# altium.net
KiCad netlist of a schematic drawn in Altium Designer
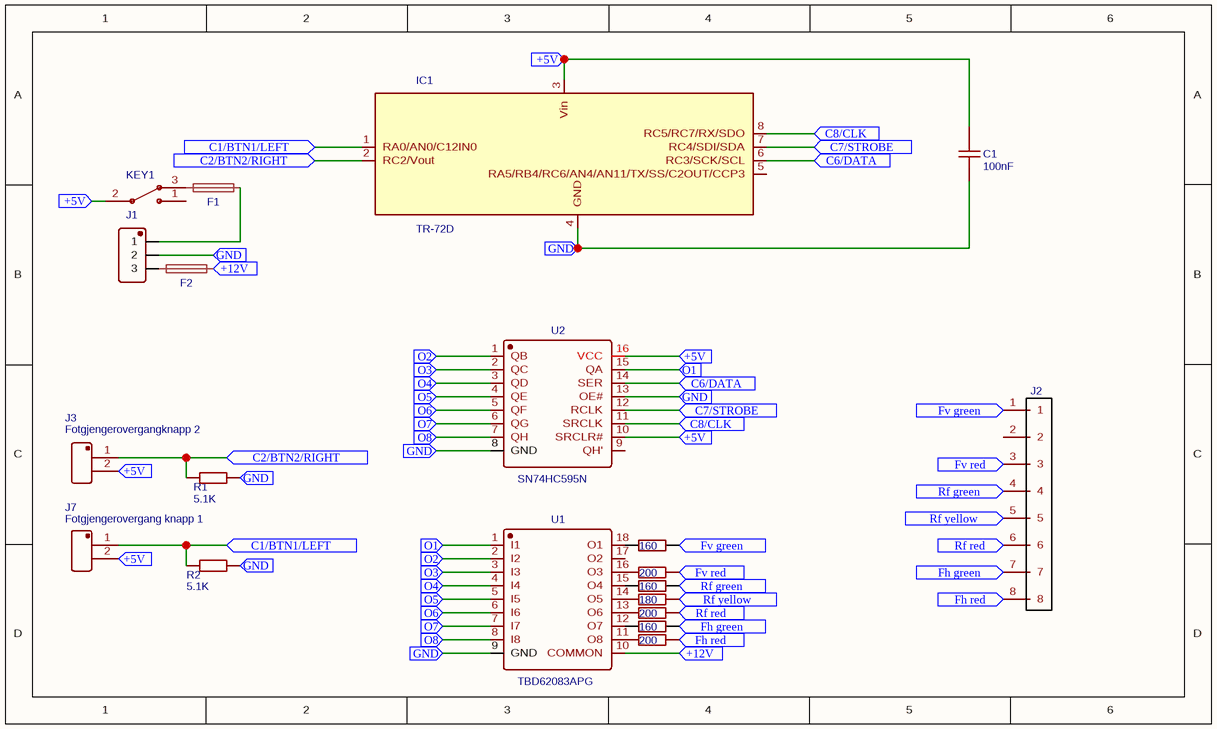
[diagram p0: altium.schdoc]

(export (version "E")
  (design (tool "Eeschema 10.0.6"))
  (components
    (comp (ref "C1")
      (value "100nF")
      (fields
        (field (name "BOM_SUPPLIER PART") "C304011")
        (field (name "BOM_MANUFACTURER PART") "1210B106K100CT")
        (field (name "CONTRIBUTOR") "LCSC")
      )
      (libsource (lib "altium-import") (part "root_3_100nF_"))
    )
    (comp (ref "F1")
      (value "NO")
      (fields
        (field (name "BOM_MANUFACTURER PART") "3403.0015.11")
        (field (name "BOM_SUPPLIER PART") "693-3403.0015.11")
        (field (name "CONTRIBUTOR") "romiksm")
      )
      (libsource (lib "altium-import") (part "root_0_NO_"))
    )
    (comp (ref "F2")
      (value "NO")
      (fields
        (field (name "BOM_MANUFACTURER PART") "3403.0015.11")
        (field (name "BOM_SUPPLIER PART") "693-3403.0015.11")
        (field (name "CONTRIBUTOR") "romiksm")
      )
      (libsource (lib "altium-import") (part "root_0_NO_"))
    )
    (comp (ref "IC1")
      (value "TR-72D")
      (fields (field (name "CONTRIBUTOR") "Simen Stensas"))
      (libsource (lib "altium-import") (part "root_0_TR-72D_"))
    )
    (comp (ref "J1")
      (value "KF127_3P_5.08")
      (fields (field (name "CONTRIBUTOR") "GrahamG"))
      (libsource (lib "altium-import") (part "root_0_KF127_3P_5.08_"))
    )
    (comp (ref "J2")
      (value "KF127-8P")
      (fields (field (name "CONTRIBUTOR") "milton.sanchez.alban"))
      (libsource (lib "altium-import") (part "root_0_KF127-8P_"))
    )
    (comp (ref "J3")
      (value "Fotgjengerovergangknapp 2")
      (fields (field (name "BOM_MANUFACTURER PART") "KF127L-5.08") (field (name "CONTRIBUTOR") "GrahamG"))
      (libsource (lib "altium-import") (part "root_0_Fotgjengerovergangknapp 2_"))
    )
    (comp (ref "J7")
      (value "Fotgjengerovergang knapp 1")
      (fields (field (name "BOM_MANUFACTURER PART") "KF127L-5.08") (field (name "CONTRIBUTOR") "GrahamG"))
      (libsource (lib "altium-import") (part "root_0_Fotgjengerovergang knapp 1_"))
    )
    (comp (ref "KEY1")
      (value "MSK-11027 Toggle Switches")
      (fields (field (name "BOM_SUPPLIER PART") "C21381"))
      (libsource (lib "altium-import") (part "root_0_MSK-11027 Toggle Switches_"))
    )
    (comp (ref "R1")
      (value "5.1K")
      (fields
        (field (name "BOM_SUPPLIER PART") "C325932")
        (field (name "BOM_MANUFACTURER PART") "RMC12065.1K1%N")
        (field (name "CONTRIBUTOR") "LCSC")
      )
      (libsource (lib "altium-import") (part "root_0_5.1K_"))
    )
    (comp (ref "R2")
      (value "5.1K")
      (fields
        (field (name "BOM_SUPPLIER PART") "C325932")
        (field (name "BOM_MANUFACTURER PART") "RMC12065.1K1%N")
        (field (name "CONTRIBUTOR") "LCSC")
      )
      (libsource (lib "altium-import") (part "root_0_5.1K_"))
    )
    (comp (ref "R8")
      (value "160")
      (fields
        (field (name "BOM_MANUFACTURER PART") "RC1206JR-07160RL")
        (field (name "BOM_SUPPLIER PART") "C137196")
      )
      (libsource (lib "altium-import") (part "root_0_160_"))
    )
    (comp (ref "R9")
      (value "160")
      (fields
        (field (name "BOM_MANUFACTURER PART") "RC1206JR-07160RL")
        (field (name "BOM_SUPPLIER PART") "C137196")
      )
      (libsource (lib "altium-import") (part "root_0_160_"))
    )
    (comp (ref "R10")
      (value "160")
      (fields
        (field (name "BOM_MANUFACTURER PART") "RC1206JR-07160RL")
        (field (name "BOM_SUPPLIER PART") "C137196")
      )
      (libsource (lib "altium-import") (part "root_0_160_"))
    )
    (comp (ref "R12")
      (value "180")
      (fields
        (field (name "BOM_SUPPLIER PART") "C204708")
        (field (name "BOM_MANUFACTURER PART") "CR1206-FX-1800ELF")
        (field (name "CONTRIBUTOR") "LCSC")
      )
      (libsource (lib "altium-import") (part "root_0_180_"))
    )
    (comp (ref "R13")
      (value "200")
      (fields
        (field (name "BOM_MANUFACTURER PART") "QR1206J200RP05")
        (field (name "BOM_SUPPLIER PART") "C149886")
        (field (name "CONTRIBUTOR") "LCSC")
      )
      (libsource (lib "altium-import") (part "root_0_200_"))
    )
    (comp (ref "R14")
      (value "200")
      (fields
        (field (name "BOM_MANUFACTURER PART") "QR1206J200RP05")
        (field (name "BOM_SUPPLIER PART") "C149886")
        (field (name "CONTRIBUTOR") "LCSC")
      )
      (libsource (lib "altium-import") (part "root_0_200_"))
    )
    (comp (ref "R15")
      (value "200")
      (fields
        (field (name "BOM_MANUFACTURER PART") "QR1206J200RP05")
        (field (name "BOM_SUPPLIER PART") "C149886")
        (field (name "CONTRIBUTOR") "LCSC")
      )
      (libsource (lib "altium-import") (part "root_0_200_"))
    )
    (comp (ref "U1")
      (value "TBD62083APG")
      (fields (field (name "BOM_SUPPLIER PART") "C114143") (field (name "CONTRIBUTOR") "LCSC"))
      (libsource (lib "altium-import") (part "root_0_TBD62083APG_"))
    )
    (comp (ref "U2")
      (value "SN74HC595N")
      (fields (field (name "BOM_SUPPLIER PART") "C78711"))
      (libsource (lib "altium-import") (part "root_0_SN74HC595N_"))
    )
  )
  (nets
    (net (code "1") (name "/+5V") (class "Default")
      (node (ref "C1") (pin "2") (pinfunction "2_2") (pintype "passive"))
      (node (ref "IC1") (pin "3") (pinfunction "Vin_3") (pintype "passive"))
      (node (ref "J3") (pin "2") (pinfunction "PIN2_2") (pintype "passive"))
      (node (ref "J7") (pin "2") (pinfunction "PIN2_2") (pintype "passive"))
      (node (ref "KEY1") (pin "2") (pinfunction "2_2") (pintype "passive"))
      (node (ref "U2") (pin "10") (pinfunction "SRCLR#_10") (pintype "passive"))
      (node (ref "U2") (pin "16") (pinfunction "VCC_16") (pintype "passive"))
    )
    (net (code "2") (name "/+12V") (class "Default")
      (node (ref "F2") (pin "2") (pinfunction "2_2") (pintype "passive"))
      (node (ref "U1") (pin "10") (pinfunction "COMMON_10") (pintype "passive"))
    )
    (net (code "3") (name "/C1{slash}BTN1{slash}LEFT") (class "Default")
      (node (ref "IC1") (pin "1") (pinfunction "RA0/AN0/C12IN0_1") (pintype "passive"))
      (node (ref "J7") (pin "1") (pinfunction "PIN1_1") (pintype "passive"))
      (node (ref "R2") (pin "1") (pinfunction "1_1") (pintype "passive"))
    )
    (net (code "4") (name "/C2{slash}BTN2{slash}RIGHT") (class "Default")
      (node (ref "IC1") (pin "2") (pinfunction "RC2/Vout_2") (pintype "passive"))
      (node (ref "J3") (pin "1") (pinfunction "PIN1_1") (pintype "passive"))
      (node (ref "R1") (pin "1") (pinfunction "1_1") (pintype "passive"))
    )
    (net (code "5") (name "/C6{slash}DATA") (class "Default")
      (node (ref "IC1") (pin "6") (pinfunction "RC3/SCK/SCL_6") (pintype "passive"))
      (node (ref "U2") (pin "14") (pinfunction "SER_14") (pintype "passive"))
    )
    (net (code "6") (name "/C7{slash}STROBE") (class "Default")
      (node (ref "IC1") (pin "7") (pinfunction "RC4/SDI/SDA_7") (pintype "passive"))
      (node (ref "U2") (pin "12") (pinfunction "RCLK_12") (pintype "passive"))
    )
    (net (code "7") (name "/C8{slash}CLK") (class "Default")
      (node (ref "IC1") (pin "8") (pinfunction "RC5/RC7/RX/SDO_8") (pintype "passive"))
      (node (ref "U2") (pin "11") (pinfunction "SRCLK_11") (pintype "passive"))
    )
    (net (code "8") (name "/Fh green") (class "Default")
      (node (ref "J2") (pin "7") (pinfunction "7_7") (pintype "passive"))
      (node (ref "R10") (pin "2") (pinfunction "2_2") (pintype "passive"))
    )
    (net (code "9") (name "/Fh red") (class "Default")
      (node (ref "J2") (pin "8") (pinfunction "8_8") (pintype "passive"))
      (node (ref "R15") (pin "2") (pinfunction "2_2") (pintype "passive"))
    )
    (net (code "10") (name "/Fv green") (class "Default")
      (node (ref "J2") (pin "1") (pinfunction "1_1") (pintype "passive"))
      (node (ref "R8") (pin "2") (pinfunction "2_2") (pintype "passive"))
    )
    (net (code "11") (name "/Fv red") (class "Default")
      (node (ref "J2") (pin "3") (pinfunction "3_3") (pintype "passive"))
      (node (ref "R13") (pin "2") (pinfunction "2_2") (pintype "passive"))
    )
    (net (code "12") (name "/GND") (class "Default")
      (node (ref "C1") (pin "1") (pinfunction "1_1") (pintype "passive"))
      (node (ref "IC1") (pin "4") (pinfunction "GND_4") (pintype "passive"))
      (node (ref "J1") (pin "2") (pinfunction "2_2") (pintype "passive"))
      (node (ref "R1") (pin "2") (pinfunction "2_2") (pintype "passive"))
      (node (ref "R2") (pin "2") (pinfunction "2_2") (pintype "passive"))
      (node (ref "U1") (pin "9") (pinfunction "GND_9") (pintype "passive"))
      (node (ref "U2") (pin "13") (pinfunction "OE#_13") (pintype "passive"))
      (node (ref "U2") (pin "8") (pinfunction "GND_8") (pintype "passive"))
    )
    (net (code "13") (name "/O1") (class "Default")
      (node (ref "U1") (pin "1") (pinfunction "I1_1") (pintype "passive"))
      (node (ref "U2") (pin "15") (pinfunction "QA_15") (pintype "passive"))
    )
    (net (code "14") (name "/O2") (class "Default")
      (node (ref "U1") (pin "2") (pinfunction "I2_2") (pintype "passive"))
      (node (ref "U2") (pin "1") (pinfunction "QB_1") (pintype "passive"))
    )
    (net (code "15") (name "/O3") (class "Default")
      (node (ref "U1") (pin "3") (pinfunction "I3_3") (pintype "passive"))
      (node (ref "U2") (pin "2") (pinfunction "QC_2") (pintype "passive"))
    )
    (net (code "16") (name "/O4") (class "Default")
      (node (ref "U1") (pin "4") (pinfunction "I4_4") (pintype "passive"))
      (node (ref "U2") (pin "3") (pinfunction "QD_3") (pintype "passive"))
    )
    (net (code "17") (name "/O5") (class "Default")
      (node (ref "U1") (pin "5") (pinfunction "I5_5") (pintype "passive"))
      (node (ref "U2") (pin "4") (pinfunction "QE_4") (pintype "passive"))
    )
    (net (code "18") (name "/O6") (class "Default")
      (node (ref "U1") (pin "6") (pinfunction "I6_6") (pintype "passive"))
      (node (ref "U2") (pin "5") (pinfunction "QF_5") (pintype "passive"))
    )
    (net (code "19") (name "/O7") (class "Default")
      (node (ref "U1") (pin "7") (pinfunction "I7_7") (pintype "passive"))
      (node (ref "U2") (pin "6") (pinfunction "QG_6") (pintype "passive"))
    )
    (net (code "20") (name "/O8") (class "Default")
      (node (ref "U1") (pin "8") (pinfunction "I8_8") (pintype "passive"))
      (node (ref "U2") (pin "7") (pinfunction "QH_7") (pintype "passive"))
    )
    (net (code "21") (name "/Rf green") (class "Default")
      (node (ref "J2") (pin "4") (pinfunction "4_4") (pintype "passive"))
      (node (ref "R9") (pin "2") (pinfunction "2_2") (pintype "passive"))
    )
    (net (code "22") (name "/Rf red") (class "Default")
      (node (ref "J2") (pin "6") (pinfunction "6_6") (pintype "passive"))
      (node (ref "R14") (pin "2") (pinfunction "2_2") (pintype "passive"))
    )
    (net (code "23") (name "/Rf yellow") (class "Default")
      (node (ref "J2") (pin "5") (pinfunction "5_5") (pintype "passive"))
      (node (ref "R12") (pin "2") (pinfunction "2_2") (pintype "passive"))
    )
    (net (code "24") (name "Net-(F1-Pad1)") (class "Default")
      (node (ref "F1") (pin "1") (pinfunction "1_1") (pintype "passive"))
      (node (ref "KEY1") (pin "3") (pinfunction "3_3") (pintype "passive"))
    )
    (net (code "25") (name "Net-(F1-Pad2)") (class "Default")
      (node (ref "F1") (pin "2") (pinfunction "2_2") (pintype "passive"))
      (node (ref "J1") (pin "1") (pinfunction "1_1") (pintype "passive"))
    )
    (net (code "26") (name "Net-(F2-Pad1)") (class "Default")
      (node (ref "F2") (pin "1") (pinfunction "1_1") (pintype "passive"))
      (node (ref "J1") (pin "3") (pinfunction "3_3") (pintype "passive"))
    )
    (net (code "27") (name "Net-(U1-O1)") (class "Default")
      (node (ref "R8") (pin "1") (pinfunction "1_1") (pintype "passive"))
      (node (ref "U1") (pin "18") (pinfunction "O1_18") (pintype "passive"))
    )
    (net (code "28") (name "Net-(U1-O3)") (class "Default")
      (node (ref "R13") (pin "1") (pinfunction "1_1") (pintype "passive"))
      (node (ref "U1") (pin "16") (pinfunction "O3_16") (pintype "passive"))
    )
    (net (code "29") (name "Net-(U1-O4)") (class "Default")
      (node (ref "R9") (pin "1") (pinfunction "1_1") (pintype "passive"))
      (node (ref "U1") (pin "15") (pinfunction "O4_15") (pintype "passive"))
    )
    (net (code "30") (name "Net-(U1-O5)") (class "Default")
      (node (ref "R12") (pin "1") (pinfunction "1_1") (pintype "passive"))
      (node (ref "U1") (pin "14") (pinfunction "O5_14") (pintype "passive"))
    )
    (net (code "31") (name "Net-(U1-O6)") (class "Default")
      (node (ref "R14") (pin "1") (pinfunction "1_1") (pintype "passive"))
      (node (ref "U1") (pin "13") (pinfunction "O6_13") (pintype "passive"))
    )
    (net (code "32") (name "Net-(U1-O7)") (class "Default")
      (node (ref "R10") (pin "1") (pinfunction "1_1") (pintype "passive"))
      (node (ref "U1") (pin "12") (pinfunction "O7_12") (pintype "passive"))
    )
    (net (code "33") (name "Net-(U1-O8)") (class "Default")
      (node (ref "R15") (pin "1") (pinfunction "1_1") (pintype "passive"))
      (node (ref "U1") (pin "11") (pinfunction "O8_11") (pintype "passive"))
    )
    (net (code "34") (name "unconnected-(IC1-RA5{slash}RB4{slash}RC6{slash}AN4{slash}AN11{slash}TX{slash}SS{slash}C2OUT{slash}CCP3-Pad5)") (class "Default")
      (node (ref "IC1") (pin "5") (pinfunction "RA5/RB4/RC6/AN4/AN11/TX/SS/C2OUT/CCP3_5") (pintype "passive"))
    )
    (net (code "35") (name "unconnected-(J2-Pad2)") (class "Default")
      (node (ref "J2") (pin "2") (pinfunction "2_2") (pintype "passive"))
    )
    (net (code "36") (name "unconnected-(KEY1-Pad1)") (class "Default")
      (node (ref "KEY1") (pin "1") (pinfunction "1_1") (pintype "passive"))
    )
    (net (code "37") (name "unconnected-(U1-O2-Pad17)") (class "Default")
      (node (ref "U1") (pin "17") (pinfunction "O2_17") (pintype "passive"))
    )
    (net (code "38") (name "unconnected-(U2-QH'-Pad9)") (class "Default")
      (node (ref "U2") (pin "9") (pinfunction "QH'_9") (pintype "passive"))
    )
  )
)
